# piezo-layer_v0_1-R001.net
KiCad netlist of a schematic drawn in EAGLE
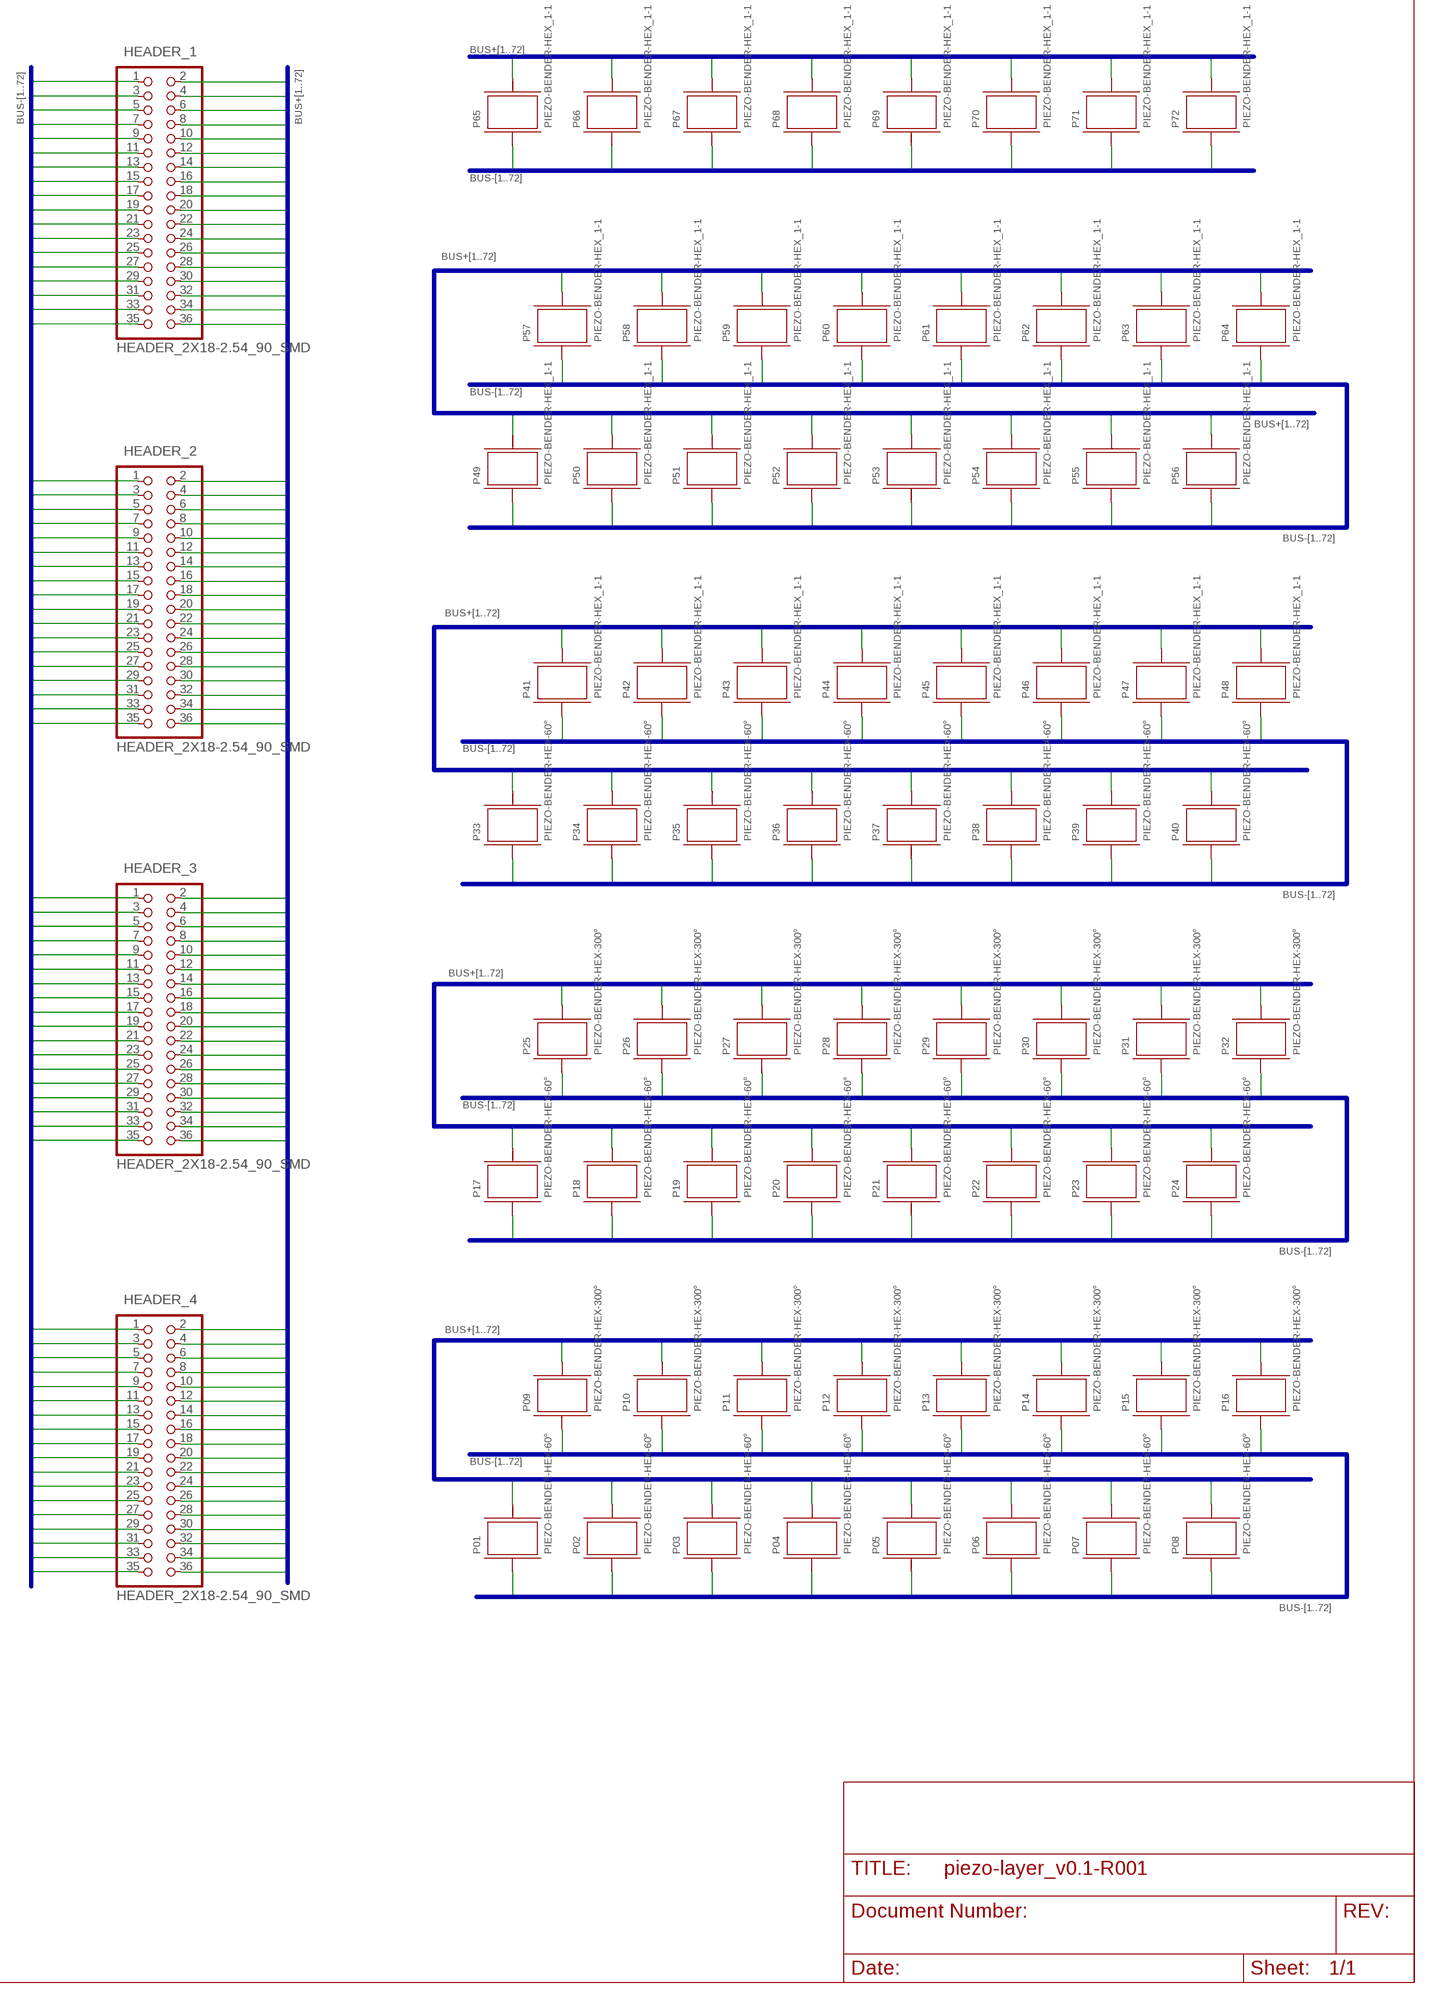
[diagram p0: schematic, sheet 1]

(export (version "E")
  (design (tool "Eeschema 10.0.6"))
  (components
    (comp (ref "HEADER_1")
      (value "HEADER_2X18-2.54_90_SMD")
      (footprint "eagle-import:2X18_2.54_90_SMD")
      (libsource (lib "eagle-import") (part "HEADER_2X18-2.54_90_SMD"))
    )
    (comp (ref "HEADER_2")
      (value "HEADER_2X18-2.54_90_SMD")
      (footprint "eagle-import:2X18_2.54_90_SMD")
      (libsource (lib "eagle-import") (part "HEADER_2X18-2.54_90_SMD"))
    )
    (comp (ref "HEADER_3")
      (value "HEADER_2X18-2.54_90_SMD")
      (footprint "eagle-import:2X18_2.54_90_SMD")
      (libsource (lib "eagle-import") (part "HEADER_2X18-2.54_90_SMD"))
    )
    (comp (ref "HEADER_4")
      (value "HEADER_2X18-2.54_90_SMD")
      (footprint "eagle-import:2X18_2.54_90_SMD")
      (libsource (lib "eagle-import") (part "HEADER_2X18-2.54_90_SMD"))
    )
    (comp (ref "P01")
      (value "PIEZO-BENDER-HEX-60°")
      (footprint "eagle-import:PIEZO-BENDER-HEX_16MM_60°")
      (libsource (lib "eagle-import") (part "PIEZO-BENDER-HEX-60°"))
    )
    (comp (ref "P02")
      (value "PIEZO-BENDER-HEX-60°")
      (footprint "eagle-import:PIEZO-BENDER-HEX_16MM_60°")
      (libsource (lib "eagle-import") (part "PIEZO-BENDER-HEX-60°"))
    )
    (comp (ref "P03")
      (value "PIEZO-BENDER-HEX-60°")
      (footprint "eagle-import:PIEZO-BENDER-HEX_16MM_60°")
      (libsource (lib "eagle-import") (part "PIEZO-BENDER-HEX-60°"))
    )
    (comp (ref "P04")
      (value "PIEZO-BENDER-HEX-60°")
      (footprint "eagle-import:PIEZO-BENDER-HEX_16MM_60°")
      (libsource (lib "eagle-import") (part "PIEZO-BENDER-HEX-60°"))
    )
    (comp (ref "P05")
      (value "PIEZO-BENDER-HEX-60°")
      (footprint "eagle-import:PIEZO-BENDER-HEX_16MM_60°")
      (libsource (lib "eagle-import") (part "PIEZO-BENDER-HEX-60°"))
    )
    (comp (ref "P06")
      (value "PIEZO-BENDER-HEX-60°")
      (footprint "eagle-import:PIEZO-BENDER-HEX_16MM_60°")
      (libsource (lib "eagle-import") (part "PIEZO-BENDER-HEX-60°"))
    )
    (comp (ref "P07")
      (value "PIEZO-BENDER-HEX-60°")
      (footprint "eagle-import:PIEZO-BENDER-HEX_16MM_60°")
      (libsource (lib "eagle-import") (part "PIEZO-BENDER-HEX-60°"))
    )
    (comp (ref "P08")
      (value "PIEZO-BENDER-HEX-60°")
      (footprint "eagle-import:PIEZO-BENDER-HEX_16MM_60°")
      (libsource (lib "eagle-import") (part "PIEZO-BENDER-HEX-60°"))
    )
    (comp (ref "P09")
      (value "PIEZO-BENDER-HEX-300°")
      (footprint "eagle-import:PIEZO-BENDER-HEX_16MM_300°")
      (libsource (lib "eagle-import") (part "PIEZO-BENDER-HEX-300°"))
    )
    (comp (ref "P10")
      (value "PIEZO-BENDER-HEX-300°")
      (footprint "eagle-import:PIEZO-BENDER-HEX_16MM_300°")
      (libsource (lib "eagle-import") (part "PIEZO-BENDER-HEX-300°"))
    )
    (comp (ref "P11")
      (value "PIEZO-BENDER-HEX-300°")
      (footprint "eagle-import:PIEZO-BENDER-HEX_16MM_300°")
      (libsource (lib "eagle-import") (part "PIEZO-BENDER-HEX-300°"))
    )
    (comp (ref "P12")
      (value "PIEZO-BENDER-HEX-300°")
      (footprint "eagle-import:PIEZO-BENDER-HEX_16MM_300°")
      (libsource (lib "eagle-import") (part "PIEZO-BENDER-HEX-300°"))
    )
    (comp (ref "P13")
      (value "PIEZO-BENDER-HEX-300°")
      (footprint "eagle-import:PIEZO-BENDER-HEX_16MM_300°")
      (libsource (lib "eagle-import") (part "PIEZO-BENDER-HEX-300°"))
    )
    (comp (ref "P14")
      (value "PIEZO-BENDER-HEX-300°")
      (footprint "eagle-import:PIEZO-BENDER-HEX_16MM_300°")
      (libsource (lib "eagle-import") (part "PIEZO-BENDER-HEX-300°"))
    )
    (comp (ref "P15")
      (value "PIEZO-BENDER-HEX-300°")
      (footprint "eagle-import:PIEZO-BENDER-HEX_16MM_300°")
      (libsource (lib "eagle-import") (part "PIEZO-BENDER-HEX-300°"))
    )
    (comp (ref "P16")
      (value "PIEZO-BENDER-HEX-300°")
      (footprint "eagle-import:PIEZO-BENDER-HEX_16MM_300°")
      (libsource (lib "eagle-import") (part "PIEZO-BENDER-HEX-300°"))
    )
    (comp (ref "P17")
      (value "PIEZO-BENDER-HEX-60°")
      (footprint "eagle-import:PIEZO-BENDER-HEX_16MM_60°")
      (libsource (lib "eagle-import") (part "PIEZO-BENDER-HEX-60°"))
    )
    (comp (ref "P18")
      (value "PIEZO-BENDER-HEX-60°")
      (footprint "eagle-import:PIEZO-BENDER-HEX_16MM_60°")
      (libsource (lib "eagle-import") (part "PIEZO-BENDER-HEX-60°"))
    )
    (comp (ref "P19")
      (value "PIEZO-BENDER-HEX-60°")
      (footprint "eagle-import:PIEZO-BENDER-HEX_16MM_60°")
      (libsource (lib "eagle-import") (part "PIEZO-BENDER-HEX-60°"))
    )
    (comp (ref "P20")
      (value "PIEZO-BENDER-HEX-60°")
      (footprint "eagle-import:PIEZO-BENDER-HEX_16MM_60°")
      (libsource (lib "eagle-import") (part "PIEZO-BENDER-HEX-60°"))
    )
    (comp (ref "P21")
      (value "PIEZO-BENDER-HEX-60°")
      (footprint "eagle-import:PIEZO-BENDER-HEX_16MM_60°")
      (libsource (lib "eagle-import") (part "PIEZO-BENDER-HEX-60°"))
    )
    (comp (ref "P22")
      (value "PIEZO-BENDER-HEX-60°")
      (footprint "eagle-import:PIEZO-BENDER-HEX_16MM_60°")
      (libsource (lib "eagle-import") (part "PIEZO-BENDER-HEX-60°"))
    )
    (comp (ref "P23")
      (value "PIEZO-BENDER-HEX-60°")
      (footprint "eagle-import:PIEZO-BENDER-HEX_16MM_60°")
      (libsource (lib "eagle-import") (part "PIEZO-BENDER-HEX-60°"))
    )
    (comp (ref "P24")
      (value "PIEZO-BENDER-HEX-60°")
      (footprint "eagle-import:PIEZO-BENDER-HEX_16MM_60°")
      (libsource (lib "eagle-import") (part "PIEZO-BENDER-HEX-60°"))
    )
    (comp (ref "P25")
      (value "PIEZO-BENDER-HEX-300°")
      (footprint "eagle-import:PIEZO-BENDER-HEX_16MM_300°")
      (libsource (lib "eagle-import") (part "PIEZO-BENDER-HEX-300°"))
    )
    (comp (ref "P26")
      (value "PIEZO-BENDER-HEX-300°")
      (footprint "eagle-import:PIEZO-BENDER-HEX_16MM_300°")
      (libsource (lib "eagle-import") (part "PIEZO-BENDER-HEX-300°"))
    )
    (comp (ref "P27")
      (value "PIEZO-BENDER-HEX-300°")
      (footprint "eagle-import:PIEZO-BENDER-HEX_16MM_300°")
      (libsource (lib "eagle-import") (part "PIEZO-BENDER-HEX-300°"))
    )
    (comp (ref "P28")
      (value "PIEZO-BENDER-HEX-300°")
      (footprint "eagle-import:PIEZO-BENDER-HEX_16MM_300°")
      (libsource (lib "eagle-import") (part "PIEZO-BENDER-HEX-300°"))
    )
    (comp (ref "P29")
      (value "PIEZO-BENDER-HEX-300°")
      (footprint "eagle-import:PIEZO-BENDER-HEX_16MM_300°")
      (libsource (lib "eagle-import") (part "PIEZO-BENDER-HEX-300°"))
    )
    (comp (ref "P30")
      (value "PIEZO-BENDER-HEX-300°")
      (footprint "eagle-import:PIEZO-BENDER-HEX_16MM_300°")
      (libsource (lib "eagle-import") (part "PIEZO-BENDER-HEX-300°"))
    )
    (comp (ref "P31")
      (value "PIEZO-BENDER-HEX-300°")
      (footprint "eagle-import:PIEZO-BENDER-HEX_16MM_300°")
      (libsource (lib "eagle-import") (part "PIEZO-BENDER-HEX-300°"))
    )
    (comp (ref "P32")
      (value "PIEZO-BENDER-HEX-300°")
      (footprint "eagle-import:PIEZO-BENDER-HEX_16MM_300°")
      (libsource (lib "eagle-import") (part "PIEZO-BENDER-HEX-300°"))
    )
    (comp (ref "P33")
      (value "PIEZO-BENDER-HEX-60°")
      (footprint "eagle-import:PIEZO-BENDER-HEX_16MM_60°")
      (libsource (lib "eagle-import") (part "PIEZO-BENDER-HEX-60°"))
    )
    (comp (ref "P34")
      (value "PIEZO-BENDER-HEX-60°")
      (footprint "eagle-import:PIEZO-BENDER-HEX_16MM_60°")
      (libsource (lib "eagle-import") (part "PIEZO-BENDER-HEX-60°"))
    )
    (comp (ref "P35")
      (value "PIEZO-BENDER-HEX-60°")
      (footprint "eagle-import:PIEZO-BENDER-HEX_16MM_60°")
      (libsource (lib "eagle-import") (part "PIEZO-BENDER-HEX-60°"))
    )
    (comp (ref "P36")
      (value "PIEZO-BENDER-HEX-60°")
      (footprint "eagle-import:PIEZO-BENDER-HEX_16MM_60°")
      (libsource (lib "eagle-import") (part "PIEZO-BENDER-HEX-60°"))
    )
    (comp (ref "P37")
      (value "PIEZO-BENDER-HEX-60°")
      (footprint "eagle-import:PIEZO-BENDER-HEX_16MM_60°")
      (libsource (lib "eagle-import") (part "PIEZO-BENDER-HEX-60°"))
    )
    (comp (ref "P38")
      (value "PIEZO-BENDER-HEX-60°")
      (footprint "eagle-import:PIEZO-BENDER-HEX_16MM_60°")
      (libsource (lib "eagle-import") (part "PIEZO-BENDER-HEX-60°"))
    )
    (comp (ref "P39")
      (value "PIEZO-BENDER-HEX-60°")
      (footprint "eagle-import:PIEZO-BENDER-HEX_16MM_60°")
      (libsource (lib "eagle-import") (part "PIEZO-BENDER-HEX-60°"))
    )
    (comp (ref "P40")
      (value "PIEZO-BENDER-HEX-60°")
      (footprint "eagle-import:PIEZO-BENDER-HEX_16MM_60°")
      (libsource (lib "eagle-import") (part "PIEZO-BENDER-HEX-60°"))
    )
    (comp (ref "P41")
      (value "PIEZO-BENDER-HEX_1-1")
      (footprint "eagle-import:PIEZO-BENDER-HEX_16MM_1+_1-")
      (libsource (lib "eagle-import") (part "PIEZO-BENDER-HEX_1-1"))
    )
    (comp (ref "P42")
      (value "PIEZO-BENDER-HEX_1-1")
      (footprint "eagle-import:PIEZO-BENDER-HEX_16MM_1+_1-")
      (libsource (lib "eagle-import") (part "PIEZO-BENDER-HEX_1-1"))
    )
    (comp (ref "P43")
      (value "PIEZO-BENDER-HEX_1-1")
      (footprint "eagle-import:PIEZO-BENDER-HEX_16MM_1+_1-")
      (libsource (lib "eagle-import") (part "PIEZO-BENDER-HEX_1-1"))
    )
    (comp (ref "P44")
      (value "PIEZO-BENDER-HEX_1-1")
      (footprint "eagle-import:PIEZO-BENDER-HEX_16MM_1+_1-")
      (libsource (lib "eagle-import") (part "PIEZO-BENDER-HEX_1-1"))
    )
    (comp (ref "P45")
      (value "PIEZO-BENDER-HEX_1-1")
      (footprint "eagle-import:PIEZO-BENDER-HEX_16MM_1+_1-")
      (libsource (lib "eagle-import") (part "PIEZO-BENDER-HEX_1-1"))
    )
    (comp (ref "P46")
      (value "PIEZO-BENDER-HEX_1-1")
      (footprint "eagle-import:PIEZO-BENDER-HEX_16MM_1+_1-")
      (libsource (lib "eagle-import") (part "PIEZO-BENDER-HEX_1-1"))
    )
    (comp (ref "P47")
      (value "PIEZO-BENDER-HEX_1-1")
      (footprint "eagle-import:PIEZO-BENDER-HEX_16MM_1+_1-")
      (libsource (lib "eagle-import") (part "PIEZO-BENDER-HEX_1-1"))
    )
    (comp (ref "P48")
      (value "PIEZO-BENDER-HEX_1-1")
      (footprint "eagle-import:PIEZO-BENDER-HEX_16MM_1+_1-")
      (libsource (lib "eagle-import") (part "PIEZO-BENDER-HEX_1-1"))
    )
    (comp (ref "P49")
      (value "PIEZO-BENDER-HEX_1-1")
      (footprint "eagle-import:PIEZO-BENDER-HEX_16MM_1+_1-")
      (libsource (lib "eagle-import") (part "PIEZO-BENDER-HEX_1-1"))
    )
    (comp (ref "P50")
      (value "PIEZO-BENDER-HEX_1-1")
      (footprint "eagle-import:PIEZO-BENDER-HEX_16MM_1+_1-")
      (libsource (lib "eagle-import") (part "PIEZO-BENDER-HEX_1-1"))
    )
    (comp (ref "P51")
      (value "PIEZO-BENDER-HEX_1-1")
      (footprint "eagle-import:PIEZO-BENDER-HEX_16MM_1+_1-")
      (libsource (lib "eagle-import") (part "PIEZO-BENDER-HEX_1-1"))
    )
    (comp (ref "P52")
      (value "PIEZO-BENDER-HEX_1-1")
      (footprint "eagle-import:PIEZO-BENDER-HEX_16MM_1+_1-")
      (libsource (lib "eagle-import") (part "PIEZO-BENDER-HEX_1-1"))
    )
    (comp (ref "P53")
      (value "PIEZO-BENDER-HEX_1-1")
      (footprint "eagle-import:PIEZO-BENDER-HEX_16MM_1+_1-")
      (libsource (lib "eagle-import") (part "PIEZO-BENDER-HEX_1-1"))
    )
    (comp (ref "P54")
      (value "PIEZO-BENDER-HEX_1-1")
      (footprint "eagle-import:PIEZO-BENDER-HEX_16MM_1+_1-")
      (libsource (lib "eagle-import") (part "PIEZO-BENDER-HEX_1-1"))
    )
    (comp (ref "P55")
      (value "PIEZO-BENDER-HEX_1-1")
      (footprint "eagle-import:PIEZO-BENDER-HEX_16MM_1+_1-")
      (libsource (lib "eagle-import") (part "PIEZO-BENDER-HEX_1-1"))
    )
    (comp (ref "P56")
      (value "PIEZO-BENDER-HEX_1-1")
      (footprint "eagle-import:PIEZO-BENDER-HEX_16MM_1+_1-")
      (libsource (lib "eagle-import") (part "PIEZO-BENDER-HEX_1-1"))
    )
    (comp (ref "P57")
      (value "PIEZO-BENDER-HEX_1-1")
      (footprint "eagle-import:PIEZO-BENDER-HEX_16MM_1+_1-")
      (libsource (lib "eagle-import") (part "PIEZO-BENDER-HEX_1-1"))
    )
    (comp (ref "P58")
      (value "PIEZO-BENDER-HEX_1-1")
      (footprint "eagle-import:PIEZO-BENDER-HEX_16MM_1+_1-")
      (libsource (lib "eagle-import") (part "PIEZO-BENDER-HEX_1-1"))
    )
    (comp (ref "P59")
      (value "PIEZO-BENDER-HEX_1-1")
      (footprint "eagle-import:PIEZO-BENDER-HEX_16MM_1+_1-")
      (libsource (lib "eagle-import") (part "PIEZO-BENDER-HEX_1-1"))
    )
    (comp (ref "P60")
      (value "PIEZO-BENDER-HEX_1-1")
      (footprint "eagle-import:PIEZO-BENDER-HEX_16MM_1+_1-")
      (libsource (lib "eagle-import") (part "PIEZO-BENDER-HEX_1-1"))
    )
    (comp (ref "P61")
      (value "PIEZO-BENDER-HEX_1-1")
      (footprint "eagle-import:PIEZO-BENDER-HEX_16MM_1+_1-")
      (libsource (lib "eagle-import") (part "PIEZO-BENDER-HEX_1-1"))
    )
    (comp (ref "P62")
      (value "PIEZO-BENDER-HEX_1-1")
      (footprint "eagle-import:PIEZO-BENDER-HEX_16MM_1+_1-")
      (libsource (lib "eagle-import") (part "PIEZO-BENDER-HEX_1-1"))
    )
    (comp (ref "P63")
      (value "PIEZO-BENDER-HEX_1-1")
      (footprint "eagle-import:PIEZO-BENDER-HEX_16MM_1+_1-")
      (libsource (lib "eagle-import") (part "PIEZO-BENDER-HEX_1-1"))
    )
    (comp (ref "P64")
      (value "PIEZO-BENDER-HEX_1-1")
      (footprint "eagle-import:PIEZO-BENDER-HEX_16MM_1+_1-")
      (libsource (lib "eagle-import") (part "PIEZO-BENDER-HEX_1-1"))
    )
    (comp (ref "P65")
      (value "PIEZO-BENDER-HEX_1-1")
      (footprint "eagle-import:PIEZO-BENDER-HEX_16MM_1+_1-")
      (libsource (lib "eagle-import") (part "PIEZO-BENDER-HEX_1-1"))
    )
    (comp (ref "P66")
      (value "PIEZO-BENDER-HEX_1-1")
      (footprint "eagle-import:PIEZO-BENDER-HEX_16MM_1+_1-")
      (libsource (lib "eagle-import") (part "PIEZO-BENDER-HEX_1-1"))
    )
    (comp (ref "P67")
      (value "PIEZO-BENDER-HEX_1-1")
      (footprint "eagle-import:PIEZO-BENDER-HEX_16MM_1+_1-")
      (libsource (lib "eagle-import") (part "PIEZO-BENDER-HEX_1-1"))
    )
    (comp (ref "P68")
      (value "PIEZO-BENDER-HEX_1-1")
      (footprint "eagle-import:PIEZO-BENDER-HEX_16MM_1+_1-")
      (libsource (lib "eagle-import") (part "PIEZO-BENDER-HEX_1-1"))
    )
    (comp (ref "P69")
      (value "PIEZO-BENDER-HEX_1-1")
      (footprint "eagle-import:PIEZO-BENDER-HEX_16MM_1+_1-")
      (libsource (lib "eagle-import") (part "PIEZO-BENDER-HEX_1-1"))
    )
    (comp (ref "P70")
      (value "PIEZO-BENDER-HEX_1-1")
      (footprint "eagle-import:PIEZO-BENDER-HEX_16MM_1+_1-")
      (libsource (lib "eagle-import") (part "PIEZO-BENDER-HEX_1-1"))
    )
    (comp (ref "P71")
      (value "PIEZO-BENDER-HEX_1-1")
      (footprint "eagle-import:PIEZO-BENDER-HEX_16MM_1+_1-")
      (libsource (lib "eagle-import") (part "PIEZO-BENDER-HEX_1-1"))
    )
    (comp (ref "P72")
      (value "PIEZO-BENDER-HEX_1-1")
      (footprint "eagle-import:PIEZO-BENDER-HEX_16MM_1+_1-")
      (libsource (lib "eagle-import") (part "PIEZO-BENDER-HEX_1-1"))
    )
  )
  (nets
    (net (code "1") (name "/BUS+1") (class "Default")
      (node (ref "HEADER_1") (pin "18") (pinfunction "18_18") (pintype "passive"))
      (node (ref "P01") (pin "TIP1") (pinfunction "+_1_TIP1") (pintype "bidirectional"))
    )
    (net (code "2") (name "/BUS+2") (class "Default")
      (node (ref "HEADER_1") (pin "36") (pinfunction "36_36") (pintype "passive"))
      (node (ref "P02") (pin "TIP1") (pinfunction "+_1_TIP1") (pintype "bidirectional"))
    )
    (net (code "3") (name "/BUS+3") (class "Default")
      (node (ref "HEADER_2") (pin "18") (pinfunction "18_18") (pintype "passive"))
      (node (ref "P03") (pin "TIP1") (pinfunction "+_1_TIP1") (pintype "bidirectional"))
    )
    (net (code "4") (name "/BUS+4") (class "Default")
      (node (ref "HEADER_2") (pin "36") (pinfunction "36_36") (pintype "passive"))
      (node (ref "P04") (pin "TIP1") (pinfunction "+_1_TIP1") (pintype "bidirectional"))
    )
    (net (code "5") (name "/BUS+5") (class "Default")
      (node (ref "HEADER_3") (pin "18") (pinfunction "18_18") (pintype "passive"))
      (node (ref "P05") (pin "TIP1") (pinfunction "+_1_TIP1") (pintype "bidirectional"))
    )
    (net (code "6") (name "/BUS+6") (class "Default")
      (node (ref "HEADER_3") (pin "36") (pinfunction "36_36") (pintype "passive"))
      (node (ref "P06") (pin "TIP1") (pinfunction "+_1_TIP1") (pintype "bidirectional"))
    )
    (net (code "7") (name "/BUS+7") (class "Default")
      (node (ref "HEADER_4") (pin "18") (pinfunction "18_18") (pintype "passive"))
      (node (ref "P07") (pin "TIP1") (pinfunction "+_1_TIP1") (pintype "bidirectional"))
    )
    (net (code "8") (name "/BUS+8") (class "Default")
      (node (ref "HEADER_4") (pin "36") (pinfunction "36_36") (pintype "passive"))
      (node (ref "P08") (pin "TIP1") (pinfunction "+_1_TIP1") (pintype "bidirectional"))
    )
    (net (code "9") (name "/BUS+9") (class "Default")
      (node (ref "HEADER_1") (pin "16") (pinfunction "16_16") (pintype "passive"))
      (node (ref "P09") (pin "TIP1") (pinfunction "+_1_TIP1") (pintype "bidirectional"))
    )
    (net (code "10") (name "/BUS+10") (class "Default")
      (node (ref "HEADER_1") (pin "34") (pinfunction "34_34") (pintype "passive"))
      (node (ref "P10") (pin "TIP1") (pinfunction "+_1_TIP1") (pintype "bidirectional"))
    )
    (net (code "11") (name "/BUS+11") (class "Default")
      (node (ref "HEADER_2") (pin "16") (pinfunction "16_16") (pintype "passive"))
      (node (ref "P11") (pin "TIP1") (pinfunction "+_1_TIP1") (pintype "bidirectional"))
    )
    (net (code "12") (name "/BUS+12") (class "Default")
      (node (ref "HEADER_2") (pin "34") (pinfunction "34_34") (pintype "passive"))
      (node (ref "P12") (pin "TIP1") (pinfunction "+_1_TIP1") (pintype "bidirectional"))
    )
    (net (code "13") (name "/BUS+13") (class "Default")
      (node (ref "HEADER_3") (pin "16") (pinfunction "16_16") (pintype "passive"))
      (node (ref "P13") (pin "TIP1") (pinfunction "+_1_TIP1") (pintype "bidirectional"))
    )
    (net (code "14") (name "/BUS+14") (class "Default")
      (node (ref "HEADER_3") (pin "34") (pinfunction "34_34") (pintype "passive"))
      (node (ref "P14") (pin "TIP1") (pinfunction "+_1_TIP1") (pintype "bidirectional"))
    )
    (net (code "15") (name "/BUS+15") (class "Default")
      (node (ref "HEADER_4") (pin "16") (pinfunction "16_16") (pintype "passive"))
      (node (ref "P15") (pin "TIP1") (pinfunction "+_1_TIP1") (pintype "bidirectional"))
    )
    (net (code "16") (name "/BUS+16") (class "Default")
      (node (ref "HEADER_4") (pin "34") (pinfunction "34_34") (pintype "passive"))
      (node (ref "P16") (pin "TIP1") (pinfunction "+_1_TIP1") (pintype "bidirectional"))
    )
    (net (code "17") (name "/BUS+17") (class "Default")
      (node (ref "HEADER_1") (pin "14") (pinfunction "14_14") (pintype "passive"))
      (node (ref "P17") (pin "TIP1") (pinfunction "+_1_TIP1") (pintype "bidirectional"))
    )
    (net (code "18") (name "/BUS+18") (class "Default")
      (node (ref "HEADER_1") (pin "32") (pinfunction "32_32") (pintype "passive"))
      (node (ref "P18") (pin "TIP1") (pinfunction "+_1_TIP1") (pintype "bidirectional"))
    )
    (net (code "19") (name "/BUS+19") (class "Default")
      (node (ref "HEADER_2") (pin "14") (pinfunction "14_14") (pintype "passive"))
      (node (ref "P19") (pin "TIP1") (pinfunction "+_1_TIP1") (pintype "bidirectional"))
    )
    (net (code "20") (name "/BUS+20") (class "Default")
      (node (ref "HEADER_2") (pin "32") (pinfunction "32_32") (pintype "passive"))
      (node (ref "P20") (pin "TIP1") (pinfunction "+_1_TIP1") (pintype "bidirectional"))
    )
    (net (code "21") (name "/BUS+21") (class "Default")
      (node (ref "HEADER_3") (pin "14") (pinfunction "14_14") (pintype "passive"))
      (node (ref "P21") (pin "TIP1") (pinfunction "+_1_TIP1") (pintype "bidirectional"))
    )
    (net (code "22") (name "/BUS+22") (class "Default")
      (node (ref "HEADER_3") (pin "32") (pinfunction "32_32") (pintype "passive"))
      (node (ref "P22") (pin "TIP1") (pinfunction "+_1_TIP1") (pintype "bidirectional"))
    )
    (net (code "23") (name "/BUS+23") (class "Default")
      (node (ref "HEADER_4") (pin "14") (pinfunction "14_14") (pintype "passive"))
      (node (ref "P23") (pin "TIP1") (pinfunction "+_1_TIP1") (pintype "bidirectional"))
    )
    (net (code "24") (name "/BUS+24") (class "Default")
      (node (ref "HEADER_4") (pin "32") (pinfunction "32_32") (pintype "passive"))
      (node (ref "P24") (pin "TIP1") (pinfunction "+_1_TIP1") (pintype "bidirectional"))
    )
    (net (code "25") (name "/BUS+25") (class "Default")
      (node (ref "HEADER_1") (pin "12") (pinfunction "12_12") (pintype "passive"))
      (node (ref "P25") (pin "TIP1") (pinfunction "+_1_TIP1") (pintype "bidirectional"))
    )
    (net (code "26") (name "/BUS+26") (class "Default")
      (node (ref "HEADER_1") (pin "30") (pinfunction "30_30") (pintype "passive"))
      (node (ref "P26") (pin "TIP1") (pinfunction "+_1_TIP1") (pintype "bidirectional"))
    )
    (net (code "27") (name "/BUS+27") (class "Default")
      (node (ref "HEADER_2") (pin "12") (pinfunction "12_12") (pintype "passive"))
      (node (ref "P27") (pin "TIP1") (pinfunction "+_1_TIP1") (pintype "bidirectional"))
    )
    (net (code "28") (name "/BUS+28") (class "Default")
      (node (ref "HEADER_2") (pin "30") (pinfunction "30_30") (pintype "passive"))
      (node (ref "P28") (pin "TIP1") (pinfunction "+_1_TIP1") (pintype "bidirectional"))
    )
    (net (code "29") (name "/BUS+29") (class "Default")
      (node (ref "HEADER_3") (pin "12") (pinfunction "12_12") (pintype "passive"))
      (node (ref "P29") (pin "TIP1") (pinfunction "+_1_TIP1") (pintype "bidirectional"))
    )
    (net (code "30") (name "/BUS+30") (class "Default")
      (node (ref "HEADER_3") (pin "30") (pinfunction "30_30") (pintype "passive"))
      (node (ref "P30") (pin "TIP1") (pinfunction "+_1_TIP1") (pintype "bidirectional"))
    )
    (net (code "31") (name "/BUS+31") (class "Default")
      (node (ref "HEADER_4") (pin "12") (pinfunction "12_12") (pintype "passive"))
      (node (ref "P31") (pin "TIP1") (pinfunction "+_1_TIP1") (pintype "bidirectional"))
    )
    (net (code "32") (name "/BUS+32") (class "Default")
      (node (ref "HEADER_4") (pin "30") (pinfunction "30_30") (pintype "passive"))
      (node (ref "P32") (pin "TIP1") (pinfunction "+_1_TIP1") (pintype "bidirectional"))
    )
    (net (code "33") (name "/BUS+33") (class "Default")
      (node (ref "HEADER_1") (pin "10") (pinfunction "10_10") (pintype "passive"))
      (node (ref "P33") (pin "TIP1") (pinfunction "+_1_TIP1") (pintype "bidirectional"))
    )
    (net (code "34") (name "/BUS+34") (class "Default")
      (node (ref "HEADER_1") (pin "28") (pinfunction "28_28") (pintype "passive"))
      (node (ref "P34") (pin "TIP1") (pinfunction "+_1_TIP1") (pintype "bidirectional"))
    )
    (net (code "35") (name "/BUS+35") (class "Default")
      (node (ref "HEADER_2") (pin "10") (pinfunction "10_10") (pintype "passive"))
      (node (ref "P35") (pin "TIP1") (pinfunction "+_1_TIP1") (pintype "bidirectional"))
    )
    (net (code "36") (name "/BUS+36") (class "Default")
      (node (ref "HEADER_2") (pin "28") (pinfunction "28_28") (pintype "passive"))
      (node (ref "P36") (pin "TIP1") (pinfunction "+_1_TIP1") (pintype "bidirectional"))
    )
    (net (code "37") (name "/BUS+37") (class "Default")
      (node (ref "HEADER_3") (pin "10") (pinfunction "10_10") (pintype "passive"))
      (node (ref "P37") (pin "TIP1") (pinfunction "+_1_TIP1") (pintype "bidirectional"))
    )
    (net (code "38") (name "/BUS+38") (class "Default")
      (node (ref "HEADER_3") (pin "28") (pinfunction "28_28") (pintype "passive"))
      (node (ref "P38") (pin "TIP1") (pinfunction "+_1_TIP1") (pintype "bidirectional"))
    )
    (net (code "39") (name "/BUS+39") (class "Default")
      (node (ref "HEADER_4") (pin "10") (pinfunction "10_10") (pintype "passive"))
      (node (ref "P39") (pin "TIP1") (pinfunction "+_1_TIP1") (pintype "bidirectional"))
    )
    (net (code "40") (name "/BUS+40") (class "Default")
      (node (ref "HEADER_4") (pin "28") (pinfunction "28_28") (pintype "passive"))
      (node (ref "P40") (pin "TIP1") (pinfunction "+_1_TIP1") (pintype "bidirectional"))
    )
    (net (code "41") (name "/BUS+41") (class "Default")
      (node (ref "HEADER_1") (pin "8") (pinfunction "8_8") (pintype "passive"))
      (node (ref "P41") (pin "TIP1") (pinfunction "+_1_TIP1") (pintype "bidirectional"))
    )
    (net (code "42") (name "/BUS+42") (class "Default")
      (node (ref "HEADER_1") (pin "26") (pinfunction "26_26") (pintype "passive"))
      (node (ref "P42") (pin "TIP1") (pinfunction "+_1_TIP1") (pintype "bidirectional"))
    )
    (net (code "43") (name "/BUS+43") (class "Default")
      (node (ref "HEADER_2") (pin "8") (pinfunction "8_8") (pintype "passive"))
      (node (ref "P43") (pin "TIP1") (pinfunction "+_1_TIP1") (pintype "bidirectional"))
    )
    (net (code "44") (name "/BUS+44") (class "Default")
      (node (ref "HEADER_2") (pin "26") (pinfunction "26_26") (pintype "passive"))
      (node (ref "P44") (pin "TIP1") (pinfunction "+_1_TIP1") (pintype "bidirectional"))
    )
    (net (code "45") (name "/BUS+45") (class "Default")
      (node (ref "HEADER_3") (pin "8") (pinfunction "8_8") (pintype "passive"))
      (node (ref "P45") (pin "TIP1") (pinfunction "+_1_TIP1") (pintype "bidirectional"))
    )
    (net (code "46") (name "/BUS+46") (class "Default")
      (node (ref "HEADER_3") (pin "26") (pinfunction "26_26") (pintype "passive"))
      (node (ref "P46") (pin "TIP1") (pinfunction "+_1_TIP1") (pintype "bidirectional"))
    )
    (net (code "47") (name "/BUS+47") (class "Default")
      (node (ref "HEADER_4") (pin "8") (pinfunction "8_8") (pintype "passive"))
      (node (ref "P47") (pin "TIP1") (pinfunction "+_1_TIP1") (pintype "bidirectional"))
    )
    (net (code "48") (name "/BUS+48") (class "Default")
      (node (ref "HEADER_4") (pin "26") (pinfunction "26_26") (pintype "passive"))
      (node (ref "P48") (pin "TIP1") (pinfunction "+_1_TIP1") (pintype "bidirectional"))
    )
    (net (code "49") (name "/BUS+49") (class "Default")
      (node (ref "HEADER_1") (pin "6") (pinfunction "6_6") (pintype "passive"))
      (node (ref "P49") (pin "TIP1") (pinfunction "+_1_TIP1") (pintype "bidirectional"))
    )
    (net (code "50") (name "/BUS+50") (class "Default")
      (node (ref "HEADER_1") (pin "24") (pinfunction "24_24") (pintype "passive"))
      (node (ref "P50") (pin "TIP1") (pinfunction "+_1_TIP1") (pintype "bidirectional"))
    )
    (net (code "51") (name "/BUS+51") (class "Default")
      (node (ref "HEADER_2") (pin "6") (pinfunction "6_6") (pintype "passive"))
      (node (ref "P51") (pin "TIP1") (pinfunction "+_1_TIP1") (pintype "bidirectional"))
    )
    (net (code "52") (name "/BUS+52") (class "Default")
      (node (ref "HEADER_2") (pin "24") (pinfunction "24_24") (pintype "passive"))
      (node (ref "P52") (pin "TIP1") (pinfunction "+_1_TIP1") (pintype "bidirectional"))
    )
    (net (code "53") (name "/BUS+53") (class "Default")
      (node (ref "HEADER_3") (pin "6") (pinfunction "6_6") (pintype "passive"))
      (node (ref "P53") (pin "TIP1") (pinfunction "+_1_TIP1") (pintype "bidirectional"))
    )
    (net (code "54") (name "/BUS+54") (class "Default")
      (node (ref "HEADER_3") (pin "24") (pinfunction "24_24") (pintype "passive"))
      (node (ref "P54") (pin "TIP1") (pinfunction "+_1_TIP1") (pintype "bidirectional"))
    )
    (net (code "55") (name "/BUS+55") (class "Default")
      (node (ref "HEADER_4") (pin "6") (pinfunction "6_6") (pintype "passive"))
      (node (ref "P55") (pin "TIP1") (pinfunction "+_1_TIP1") (pintype "bidirectional"))
    )
    (net (code "56") (name "/BUS+56") (class "Default")
      (node (ref "HEADER_4") (pin "24") (pinfunction "24_24") (pintype "passive"))
      (node (ref "P56") (pin "TIP1") (pinfunction "+_1_TIP1") (pintype "bidirectional"))
    )
    (net (code "57") (name "/BUS+57") (class "Default")
      (node (ref "HEADER_1") (pin "4") (pinfunction "4_4") (pintype "passive"))
      (node (ref "P57") (pin "TIP1") (pinfunction "+_1_TIP1") (pintype "bidirectional"))
    )
    (net (code "58") (name "/BUS+58") (class "Default")
      (node (ref "HEADER_1") (pin "22") (pinfunction "22_22") (pintype "passive"))
      (node (ref "P58") (pin "TIP1") (pinfunction "+_1_TIP1") (pintype "bidirectional"))
    )
    (net (code "59") (name "/BUS+59") (class "Default")
      (node (ref "HEADER_2") (pin "4") (pinfunction "4_4") (pintype "passive"))
      (node (ref "P59") (pin "TIP1") (pinfunction "+_1_TIP1") (pintype "bidirectional"))
    )
    (net (code "60") (name "/BUS+60") (class "Default")
      (node (ref "HEADER_2") (pin "22") (pinfunction "22_22") (pintype "passive"))
      (node (ref "P60") (pin "TIP1") (pinfunction "+_1_TIP1") (pintype "bidirectional"))
    )
    (net (code "61") (name "/BUS+61") (class "Default")
      (node (ref "HEADER_3") (pin "4") (pinfunction "4_4") (pintype "passive"))
      (node (ref "P61") (pin "TIP1") (pinfunction "+_1_TIP1") (pintype "bidirectional"))
    )
    (net (code "62") (name "/BUS+62") (class "Default")
      (node (ref "HEADER_3") (pin "22") (pinfunction "22_22") (pintype "passive"))
      (node (ref "P62") (pin "TIP1") (pinfunction "+_1_TIP1") (pintype "bidirectional"))
    )
    (net (code "63") (name "/BUS+63") (class "Default")
      (node (ref "HEADER_4") (pin "4") (pinfunction "4_4") (pintype "passive"))
      (node (ref "P63") (pin "TIP1") (pinfunction "+_1_TIP1") (pintype "bidirectional"))
    )
    (net (code "64") (name "/BUS+64") (class "Default")
      (node (ref "HEADER_4") (pin "22") (pinfunction "22_22") (pintype "passive"))
      (node (ref "P64") (pin "TIP1") (pinfunction "+_1_TIP1") (pintype "bidirectional"))
    )
    (net (code "65") (name "/BUS+65") (class "Default")
      (node (ref "HEADER_1") (pin "2") (pinfunction "2_2") (pintype "passive"))
      (node (ref "P65") (pin "TIP1") (pinfunction "+_1_TIP1") (pintype "bidirectional"))
    )
    (net (code "66") (name "/BUS+66") (class "Default")
      (node (ref "HEADER_1") (pin "20") (pinfunction "20_20") (pintype "passive"))
      (node (ref "P66") (pin "TIP1") (pinfunction "+_1_TIP1") (pintype "bidirectional"))
    )
    (net (code "67") (name "/BUS+67") (class "Default")
      (node (ref "HEADER_2") (pin "2") (pinfunction "2_2") (pintype "passive"))
      (node (ref "P67") (pin "TIP1") (pinfunction "+_1_TIP1") (pintype "bidirectional"))
    )
    (net (code "68") (name "/BUS+68") (class "Default")
      (node (ref "HEADER_2") (pin "20") (pinfunction "20_20") (pintype "passive"))
      (node (ref "P68") (pin "TIP1") (pinfunction "+_1_TIP1") (pintype "bidirectional"))
    )
    (net (code "69") (name "/BUS+69") (class "Default")
      (node (ref "HEADER_3") (pin "2") (pinfunction "2_2") (pintype "passive"))
      (node (ref "P69") (pin "TIP1") (pinfunction "+_1_TIP1") (pintype "bidirectional"))
    )
    (net (code "70") (name "/BUS+70") (class "Default")
      (node (ref "HEADER_3") (pin "20") (pinfunction "20_20") (pintype "passive"))
      (node (ref "P70") (pin "TIP1") (pinfunction "+_1_TIP1") (pintype "bidirectional"))
    )
    (net (code "71") (name "/BUS+71") (class "Default")
      (node (ref "HEADER_4") (pin "2") (pinfunction "2_2") (pintype "passive"))
      (node (ref "P71") (pin "TIP1") (pinfunction "+_1_TIP1") (pintype "bidirectional"))
    )
    (net (code "72") (name "/BUS+72") (class "Default")
      (node (ref "HEADER_4") (pin "20") (pinfunction "20_20") (pintype "passive"))
      (node (ref "P72") (pin "TIP1") (pinfunction "+_1_TIP1") (pintype "bidirectional"))
    )
    (net (code "74") (name "/BUS-1") (class "Default")
      (node (ref "HEADER_1") (pin "17") (pinfunction "17_17") (pintype "passive"))
      (node (ref "P01") (pin "PAD1") (pinfunction "-_1_PAD1") (pintype "bidirectional"))
    )
    (net (code "75") (name "/BUS-2") (class "Default")
      (node (ref "HEADER_1") (pin "35") (pinfunction "35_35") (pintype "passive"))
      (node (ref "P02") (pin "PAD1") (pinfunction "-_1_PAD1") (pintype "bidirectional"))
    )
    (net (code "76") (name "/BUS-3") (class "Default")
      (node (ref "HEADER_2") (pin "17") (pinfunction "17_17") (pintype "passive"))
      (node (ref "P03") (pin "PAD1") (pinfunction "-_1_PAD1") (pintype "bidirectional"))
    )
    (net (code "77") (name "/BUS-4") (class "Default")
      (node (ref "HEADER_2") (pin "35") (pinfunction "35_35") (pintype "passive"))
      (node (ref "P04") (pin "PAD1") (pinfunction "-_1_PAD1") (pintype "bidirectional"))
    )
    (net (code "78") (name "/BUS-5") (class "Default")
      (node (ref "HEADER_3") (pin "17") (pinfunction "17_17") (pintype "passive"))
      (node (ref "P05") (pin "PAD1") (pinfunction "-_1_PAD1") (pintype "bidirectional"))
    )
    (net (code "79") (name "/BUS-6") (class "Default")
      (node (ref "HEADER_3") (pin "35") (pinfunction "35_35") (pintype "passive"))
      (node (ref "P06") (pin "PAD1") (pinfunction "-_1_PAD1") (pintype "bidirectional"))
    )
    (net (code "80") (name "/BUS-7") (class "Default")
      (node (ref "HEADER_4") (pin "17") (pinfunction "17_17") (pintype "passive"))
      (node (ref "P07") (pin "PAD1") (pinfunction "-_1_PAD1") (pintype "bidirectional"))
    )
    (net (code "81") (name "/BUS-8") (class "Default")
      (node (ref "HEADER_4") (pin "35") (pinfunction "35_35") (pintype "passive"))
      (node (ref "P08") (pin "PAD1") (pinfunction "-_1_PAD1") (pintype "bidirectional"))
    )
    (net (code "82") (name "/BUS-9") (class "Default")
      (node (ref "HEADER_1") (pin "15") (pinfunction "15_15") (pintype "passive"))
      (node (ref "P09") (pin "PAD1") (pinfunction "-_1_PAD1") (pintype "bidirectional"))
    )
    (net (code "83") (name "/BUS-10") (class "Default")
      (node (ref "HEADER_1") (pin "33") (pinfunction "33_33") (pintype "passive"))
      (node (ref "P10") (pin "PAD1") (pinfunction "-_1_PAD1") (pintype "bidirectional"))
    )
    (net (code "84") (name "/BUS-11") (class "Default")
      (node (ref "HEADER_2") (pin "15") (pinfunction "15_15") (pintype "passive"))
      (node (ref "P11") (pin "PAD1") (pinfunction "-_1_PAD1") (pintype "bidirectional"))
    )
    (net (code "85") (name "/BUS-12") (class "Default")
      (node (ref "HEADER_2") (pin "33") (pinfunction "33_33") (pintype "passive"))
      (node (ref "P12") (pin "PAD1") (pinfunction "-_1_PAD1") (pintype "bidirectional"))
    )
    (net (code "86") (name "/BUS-13") (class "Default")
      (node (ref "HEADER_3") (pin "15") (pinfunction "15_15") (pintype "passive"))
      (node (ref "P13") (pin "PAD1") (pinfunction "-_1_PAD1") (pintype "bidirectional"))
    )
    (net (code "87") (name "/BUS-14") (class "Default")
      (node (ref "HEADER_3") (pin "33") (pinfunction "33_33") (pintype "passive"))
      (node (ref "P14") (pin "PAD1") (pinfunction "-_1_PAD1") (pintype "bidirectional"))
    )
    (net (code "88") (name "/BUS-15") (class "Default")
      (node (ref "HEADER_4") (pin "15") (pinfunction "15_15") (pintype "passive"))
      (node (ref "P15") (pin "PAD1") (pinfunction "-_1_PAD1") (pintype "bidirectional"))
    )
    (net (code "89") (name "/BUS-16") (class "Default")
      (node (ref "HEADER_4") (pin "33") (pinfunction "33_33") (pintype "passive"))
      (node (ref "P16") (pin "PAD1") (pinfunction "-_1_PAD1") (pintype "bidirectional"))
    )
    (net (code "90") (name "/BUS-17") (class "Default")
      (node (ref "HEADER_1") (pin "13") (pinfunction "13_13") (pintype "passive"))
      (node (ref "P17") (pin "PAD1") (pinfunction "-_1_PAD1") (pintype "bidirectional"))
    )
    (net (code "91") (name "/BUS-18") (class "Default")
      (node (ref "HEADER_1") (pin "31") (pinfunction "31_31") (pintype "passive"))
      (node (ref "P18") (pin "PAD1") (pinfunction "-_1_PAD1") (pintype "bidirectional"))
    )
    (net (code "92") (name "/BUS-19") (class "Default")
      (node (ref "HEADER_2") (pin "13") (pinfunction "13_13") (pintype "passive"))
      (node (ref "P19") (pin "PAD1") (pinfunction "-_1_PAD1") (pintype "bidirectional"))
    )
    (net (code "93") (name "/BUS-20") (class "Default")
      (node (ref "HEADER_2") (pin "31") (pinfunction "31_31") (pintype "passive"))
      (node (ref "P20") (pin "PAD1") (pinfunction "-_1_PAD1") (pintype "bidirectional"))
    )
    (net (code "94") (name "/BUS-21") (class "Default")
      (node (ref "HEADER_3") (pin "13") (pinfunction "13_13") (pintype "passive"))
      (node (ref "P21") (pin "PAD1") (pinfunction "-_1_PAD1") (pintype "bidirectional"))
    )
    (net (code "95") (name "/BUS-22") (class "Default")
      (node (ref "HEADER_3") (pin "31") (pinfunction "31_31") (pintype "passive"))
      (node (ref "P22") (pin "PAD1") (pinfunction "-_1_PAD1") (pintype "bidirectional"))
    )
    (net (code "96") (name "/BUS-23") (class "Default")
      (node (ref "HEADER_4") (pin "13") (pinfunction "13_13") (pintype "passive"))
      (node (ref "P23") (pin "PAD1") (pinfunction "-_1_PAD1") (pintype "bidirectional"))
    )
    (net (code "97") (name "/BUS-24") (class "Default")
      (node (ref "HEADER_4") (pin "31") (pinfunction "31_31") (pintype "passive"))
      (node (ref "P24") (pin "PAD1") (pinfunction "-_1_PAD1") (pintype "bidirectional"))
    )
    (net (code "98") (name "/BUS-25") (class "Default")
      (node (ref "HEADER_1") (pin "11") (pinfunction "11_11") (pintype "passive"))
      (node (ref "P25") (pin "PAD1") (pinfunction "-_1_PAD1") (pintype "bidirectional"))
    )
    (net (code "99") (name "/BUS-26") (class "Default")
      (node (ref "HEADER_1") (pin "29") (pinfunction "29_29") (pintype "passive"))
      (node (ref "P26") (pin "PAD1") (pinfunction "-_1_PAD1") (pintype "bidirectional"))
    )
    (net (code "100") (name "/BUS-27") (class "Default")
      (node (ref "HEADER_2") (pin "11") (pinfunction "11_11") (pintype "passive"))
      (node (ref "P27") (pin "PAD1") (pinfunction "-_1_PAD1") (pintype "bidirectional"))
    )
    (net (code "101") (name "/BUS-28") (class "Default")
      (node (ref "HEADER_2") (pin "29") (pinfunction "29_29") (pintype "passive"))
      (node (ref "P28") (pin "PAD1") (pinfunction "-_1_PAD1") (pintype "bidirectional"))
    )
    (net (code "102") (name "/BUS-29") (class "Default")
      (node (ref "HEADER_3") (pin "11") (pinfunction "11_11") (pintype "passive"))
      (node (ref "P29") (pin "PAD1") (pinfunction "-_1_PAD1") (pintype "bidirectional"))
    )
    (net (code "103") (name "/BUS-30") (class "Default")
      (node (ref "HEADER_3") (pin "29") (pinfunction "29_29") (pintype "passive"))
      (node (ref "P30") (pin "PAD1") (pinfunction "-_1_PAD1") (pintype "bidirectional"))
    )
    (net (code "104") (name "/BUS-31") (class "Default")
      (node (ref "HEADER_4") (pin "11") (pinfunction "11_11") (pintype "passive"))
      (node (ref "P31") (pin "PAD1") (pinfunction "-_1_PAD1") (pintype "bidirectional"))
    )
    (net (code "105") (name "/BUS-32") (class "Default")
      (node (ref "HEADER_4") (pin "29") (pinfunction "29_29") (pintype "passive"))
      (node (ref "P32") (pin "PAD1") (pinfunction "-_1_PAD1") (pintype "bidirectional"))
    )
    (net (code "106") (name "/BUS-33") (class "Default")
      (node (ref "HEADER_1") (pin "9") (pinfunction "9_9") (pintype "passive"))
      (node (ref "P33") (pin "PAD1") (pinfunction "-_1_PAD1") (pintype "bidirectional"))
    )
    (net (code "107") (name "/BUS-34") (class "Default")
      (node (ref "HEADER_1") (pin "27") (pinfunction "27_27") (pintype "passive"))
      (node (ref "P34") (pin "PAD1") (pinfunction "-_1_PAD1") (pintype "bidirectional"))
    )
    (net (code "108") (name "/BUS-35") (class "Default")
      (node (ref "HEADER_2") (pin "9") (pinfunction "9_9") (pintype "passive"))
      (node (ref "P35") (pin "PAD1") (pinfunction "-_1_PAD1") (pintype "bidirectional"))
    )
    (net (code "109") (name "/BUS-36") (class "Default")
      (node (ref "HEADER_2") (pin "27") (pinfunction "27_27") (pintype "passive"))
      (node (ref "P36") (pin "PAD1") (pinfunction "-_1_PAD1") (pintype "bidirectional"))
    )
    (net (code "110") (name "/BUS-37") (class "Default")
      (node (ref "HEADER_3") (pin "9") (pinfunction "9_9") (pintype "passive"))
      (node (ref "P37") (pin "PAD1") (pinfunction "-_1_PAD1") (pintype "bidirectional"))
    )
    (net (code "111") (name "/BUS-38") (class "Default")
      (node (ref "HEADER_3") (pin "27") (pinfunction "27_27") (pintype "passive"))
      (node (ref "P38") (pin "PAD1") (pinfunction "-_1_PAD1") (pintype "bidirectional"))
    )
    (net (code "112") (name "/BUS-39") (class "Default")
      (node (ref "HEADER_4") (pin "9") (pinfunction "9_9") (pintype "passive"))
      (node (ref "P39") (pin "PAD1") (pinfunction "-_1_PAD1") (pintype "bidirectional"))
    )
    (net (code "113") (name "/BUS-40") (class "Default")
      (node (ref "HEADER_4") (pin "27") (pinfunction "27_27") (pintype "passive"))
      (node (ref "P40") (pin "PAD1") (pinfunction "-_1_PAD1") (pintype "bidirectional"))
    )
    (net (code "114") (name "/BUS-41") (class "Default")
      (node (ref "HEADER_1") (pin "7") (pinfunction "7_7") (pintype "passive"))
      (node (ref "P41") (pin "PAD1") (pinfunction "-_1_PAD1") (pintype "bidirectional"))
    )
    (net (code "115") (name "/BUS-42") (class "Default")
      (node (ref "HEADER_1") (pin "25") (pinfunction "25_25") (pintype "passive"))
      (node (ref "P42") (pin "PAD1") (pinfunction "-_1_PAD1") (pintype "bidirectional"))
    )
    (net (code "116") (name "/BUS-43") (class "Default")
      (node (ref "HEADER_2") (pin "7") (pinfunction "7_7") (pintype "passive"))
      (node (ref "P43") (pin "PAD1") (pinfunction "-_1_PAD1") (pintype "bidirectional"))
    )
    (net (code "117") (name "/BUS-44") (class "Default")
      (node (ref "HEADER_2") (pin "25") (pinfunction "25_25") (pintype "passive"))
      (node (ref "P44") (pin "PAD1") (pinfunction "-_1_PAD1") (pintype "bidirectional"))
    )
    (net (code "118") (name "/BUS-45") (class "Default")
      (node (ref "HEADER_3") (pin "7") (pinfunction "7_7") (pintype "passive"))
      (node (ref "P45") (pin "PAD1") (pinfunction "-_1_PAD1") (pintype "bidirectional"))
    )
    (net (code "119") (name "/BUS-46") (class "Default")
      (node (ref "HEADER_3") (pin "25") (pinfunction "25_25") (pintype "passive"))
      (node (ref "P46") (pin "PAD1") (pinfunction "-_1_PAD1") (pintype "bidirectional"))
    )
    (net (code "120") (name "/BUS-47") (class "Default")
      (node (ref "HEADER_4") (pin "7") (pinfunction "7_7") (pintype "passive"))
      (node (ref "P47") (pin "PAD1") (pinfunction "-_1_PAD1") (pintype "bidirectional"))
    )
    (net (code "121") (name "/BUS-48") (class "Default")
      (node (ref "HEADER_4") (pin "25") (pinfunction "25_25") (pintype "passive"))
      (node (ref "P48") (pin "PAD1") (pinfunction "-_1_PAD1") (pintype "bidirectional"))
    )
    (net (code "122") (name "/BUS-49") (class "Default")
      (node (ref "HEADER_1") (pin "5") (pinfunction "5_5") (pintype "passive"))
      (node (ref "P49") (pin "PAD1") (pinfunction "-_1_PAD1") (pintype "bidirectional"))
    )
    (net (code "123") (name "/BUS-50") (class "Default")
      (node (ref "HEADER_1") (pin "23") (pinfunction "23_23") (pintype "passive"))
      (node (ref "P50") (pin "PAD1") (pinfunction "-_1_PAD1") (pintype "bidirectional"))
    )
    (net (code "124") (name "/BUS-51") (class "Default")
      (node (ref "HEADER_2") (pin "5") (pinfunction "5_5") (pintype "passive"))
      (node (ref "P51") (pin "PAD1") (pinfunction "-_1_PAD1") (pintype "bidirectional"))
    )
    (net (code "125") (name "/BUS-52") (class "Default")
      (node (ref "HEADER_2") (pin "23") (pinfunction "23_23") (pintype "passive"))
      (node (ref "P52") (pin "PAD1") (pinfunction "-_1_PAD1") (pintype "bidirectional"))
    )
    (net (code "126") (name "/BUS-53") (class "Default")
      (node (ref "HEADER_3") (pin "5") (pinfunction "5_5") (pintype "passive"))
      (node (ref "P53") (pin "PAD1") (pinfunction "-_1_PAD1") (pintype "bidirectional"))
    )
    (net (code "127") (name "/BUS-54") (class "Default")
      (node (ref "HEADER_3") (pin "23") (pinfunction "23_23") (pintype "passive"))
      (node (ref "P54") (pin "PAD1") (pinfunction "-_1_PAD1") (pintype "bidirectional"))
    )
    (net (code "128") (name "/BUS-55") (class "Default")
      (node (ref "HEADER_4") (pin "5") (pinfunction "5_5") (pintype "passive"))
      (node (ref "P55") (pin "PAD1") (pinfunction "-_1_PAD1") (pintype "bidirectional"))
    )
    (net (code "129") (name "/BUS-56") (class "Default")
      (node (ref "HEADER_4") (pin "23") (pinfunction "23_23") (pintype "passive"))
      (node (ref "P56") (pin "PAD1") (pinfunction "-_1_PAD1") (pintype "bidirectional"))
    )
    (net (code "130") (name "/BUS-57") (class "Default")
      (node (ref "HEADER_1") (pin "3") (pinfunction "3_3") (pintype "passive"))
      (node (ref "P57") (pin "PAD1") (pinfunction "-_1_PAD1") (pintype "bidirectional"))
    )
    (net (code "131") (name "/BUS-58") (class "Default")
      (node (ref "HEADER_1") (pin "21") (pinfunction "21_21") (pintype "passive"))
      (node (ref "P58") (pin "PAD1") (pinfunction "-_1_PAD1") (pintype "bidirectional"))
    )
    (net (code "132") (name "/BUS-59") (class "Default")
      (node (ref "HEADER_2") (pin "3") (pinfunction "3_3") (pintype "passive"))
      (node (ref "P59") (pin "PAD1") (pinfunction "-_1_PAD1") (pintype "bidirectional"))
    )
    (net (code "133") (name "/BUS-60") (class "Default")
      (node (ref "HEADER_2") (pin "21") (pinfunction "21_21") (pintype "passive"))
      (node (ref "P60") (pin "PAD1") (pinfunction "-_1_PAD1") (pintype "bidirectional"))
    )
    (net (code "134") (name "/BUS-61") (class "Default")
      (node (ref "HEADER_3") (pin "3") (pinfunction "3_3") (pintype "passive"))
      (node (ref "P61") (pin "PAD1") (pinfunction "-_1_PAD1") (pintype "bidirectional"))
    )
    (net (code "135") (name "/BUS-62") (class "Default")
      (node (ref "HEADER_3") (pin "21") (pinfunction "21_21") (pintype "passive"))
      (node (ref "P62") (pin "PAD1") (pinfunction "-_1_PAD1") (pintype "bidirectional"))
    )
    (net (code "136") (name "/BUS-63") (class "Default")
      (node (ref "HEADER_4") (pin "3") (pinfunction "3_3") (pintype "passive"))
      (node (ref "P63") (pin "PAD1") (pinfunction "-_1_PAD1") (pintype "bidirectional"))
    )
    (net (code "137") (name "/BUS-64") (class "Default")
      (node (ref "HEADER_4") (pin "21") (pinfunction "21_21") (pintype "passive"))
      (node (ref "P64") (pin "PAD1") (pinfunction "-_1_PAD1") (pintype "bidirectional"))
    )
    (net (code "138") (name "/BUS-65") (class "Default")
      (node (ref "HEADER_1") (pin "1") (pinfunction "1_1") (pintype "passive"))
      (node (ref "P65") (pin "PAD1") (pinfunction "-_1_PAD1") (pintype "bidirectional"))
    )
    (net (code "139") (name "/BUS-66") (class "Default")
      (node (ref "HEADER_1") (pin "19") (pinfunction "19_19") (pintype "passive"))
      (node (ref "P66") (pin "PAD1") (pinfunction "-_1_PAD1") (pintype "bidirectional"))
    )
    (net (code "140") (name "/BUS-67") (class "Default")
      (node (ref "HEADER_2") (pin "1") (pinfunction "1_1") (pintype "passive"))
      (node (ref "P67") (pin "PAD1") (pinfunction "-_1_PAD1") (pintype "bidirectional"))
    )
    (net (code "141") (name "/BUS-68") (class "Default")
      (node (ref "HEADER_2") (pin "19") (pinfunction "19_19") (pintype "passive"))
      (node (ref "P68") (pin "PAD1") (pinfunction "-_1_PAD1") (pintype "bidirectional"))
    )
    (net (code "142") (name "/BUS-69") (class "Default")
      (node (ref "HEADER_3") (pin "1") (pinfunction "1_1") (pintype "passive"))
      (node (ref "P69") (pin "PAD1") (pinfunction "-_1_PAD1") (pintype "bidirectional"))
    )
    (net (code "143") (name "/BUS-70") (class "Default")
      (node (ref "HEADER_3") (pin "19") (pinfunction "19_19") (pintype "passive"))
      (node (ref "P70") (pin "PAD1") (pinfunction "-_1_PAD1") (pintype "bidirectional"))
    )
    (net (code "144") (name "/BUS-71") (class "Default")
      (node (ref "HEADER_4") (pin "1") (pinfunction "1_1") (pintype "passive"))
      (node (ref "P71") (pin "PAD1") (pinfunction "-_1_PAD1") (pintype "bidirectional"))
    )
    (net (code "145") (name "/BUS-72") (class "Default")
      (node (ref "HEADER_4") (pin "19") (pinfunction "19_19") (pintype "passive"))
      (node (ref "P72") (pin "PAD1") (pinfunction "-_1_PAD1") (pintype "bidirectional"))
    )
  )
)
